# SP485.net
KiCad netlist of a schematic drawn in Altium Designer
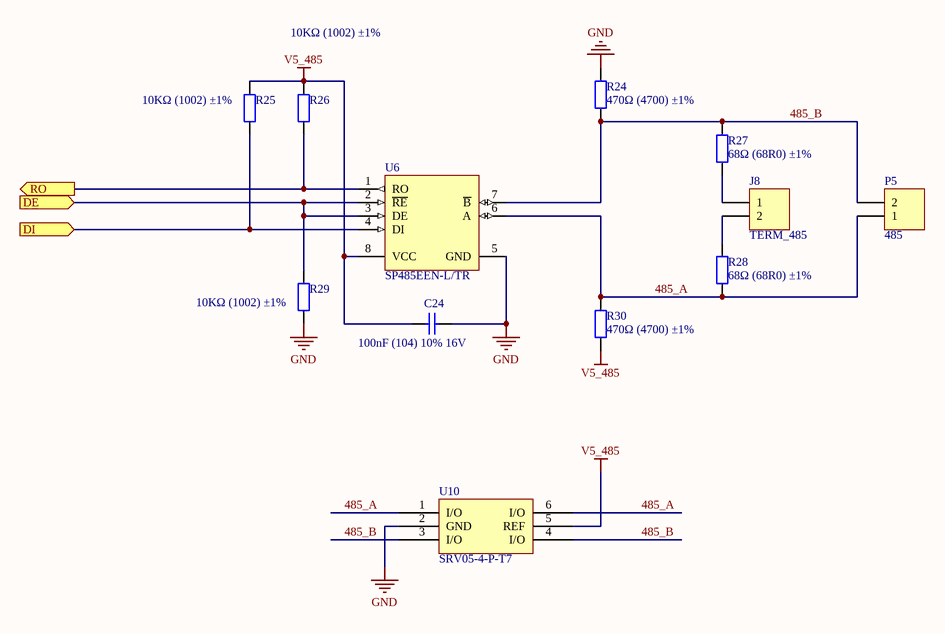
[diagram p0: SP485.SchDoc]

(export (version "E")
  (design (tool "Eeschema 10.0.6"))
  (components
    (comp (ref "C24")
      (value "100nF (104) 10% 16V")
      (footprint "0402_C")
      (description "贴片电容")
      (libsource (lib "Miscellaneous Devices LC") (part "0402 100nF (104) 10% 16V"))
    )
    (comp (ref "J8")
      (value "TERM_485")
      (footprint "HDR1X2")
      (description "Header, 2-Pin")
      (fields (field (name "PUBLISHER") "Altium Limited"))
      (libsource (lib "Miscellaneous Connectors") (part "Header 2"))
    )
    (comp (ref "P5")
      (value "485")
      (footprint "WJ2EDGRC-5.08-2PxxR")
      (description "Header, 2-Pin")
      (fields (field (name "PUBLISHER") "Altium Limited"))
      (libsource (lib "") (part "Header 2_1"))
    )
    (comp (ref "R24")
      (value "470Ω (4700) ±1%")
      (footprint "0603_R")
      (description "贴片电阻")
      (libsource (lib "Miscellaneous Devices LC") (part "0603 470Ω (4700) 1%"))
    )
    (comp (ref "R25")
      (value "10KΩ (1002) ±1%")
      (footprint "0402_R")
      (description "贴片电阻")
      (libsource (lib "Miscellaneous Devices LC") (part "0402 10KΩ (1002) 1%"))
    )
    (comp (ref "R26")
      (value "10KΩ (1002) ±1%")
      (footprint "0402_R")
      (description "贴片电阻")
      (libsource (lib "Miscellaneous Devices LC") (part "0402 10KΩ (1002) 1%"))
    )
    (comp (ref "R27")
      (value "68Ω (68R0) ±1%")
      (footprint "0603_R")
      (description "贴片电阻")
      (libsource (lib "Miscellaneous Devices LC") (part "0603 68Ω (68R0) 1%"))
    )
    (comp (ref "R28")
      (value "68Ω (68R0) ±1%")
      (footprint "0603_R")
      (description "贴片电阻")
      (libsource (lib "Miscellaneous Devices LC") (part "0603 68Ω (68R0) 1%"))
    )
    (comp (ref "R29")
      (value "10KΩ (1002) ±1%")
      (footprint "0402_R")
      (description "贴片电阻")
      (libsource (lib "Miscellaneous Devices LC") (part "0402 10KΩ (1002) 1%"))
    )
    (comp (ref "R30")
      (value "470Ω (4700) ±1%")
      (footprint "0603_R")
      (description "贴片电阻")
      (libsource (lib "Miscellaneous Devices LC") (part "0603 470Ω (4700) 1%"))
    )
    (comp (ref "U6")
      (value "SP485EEN-L/TR")
      (footprint "SOIC-8_150mil")
      (description "RS-485/RS-422")
      (libsource (lib "Miscellaneous Devices LC") (part "SP485EEN-L/TR_[C6855]"))
    )
    (comp (ref "U10")
      (value "SRV05-4-P-T7")
      (footprint "SOT-23-6")
      (description "TVS")
      (libsource (lib "Miscellaneous Devices LC") (part "SRV05-4-P-T7_[C85364]"))
    )
  )
  (nets
    (net (code "1") (name "/485_A") (class "Default")
      (node (ref "P5") (pin "1") (pinfunction "1_1") (pintype "passive"))
      (node (ref "R28") (pin "1") (pinfunction "1_1") (pintype "passive"))
      (node (ref "R30") (pin "2") (pinfunction "2_2") (pintype "passive"))
      (node (ref "U10") (pin "1") (pinfunction "I/O_1") (pintype "passive"))
      (node (ref "U10") (pin "6") (pinfunction "I/O_6") (pintype "passive"))
      (node (ref "U6") (pin "6") (pinfunction "A_6") (pintype "bidirectional"))
    )
    (net (code "2") (name "/485_B") (class "Default")
      (node (ref "P5") (pin "2") (pinfunction "2_2") (pintype "passive"))
      (node (ref "R24") (pin "1") (pinfunction "1_1") (pintype "passive"))
      (node (ref "R27") (pin "2") (pinfunction "2_2") (pintype "passive"))
      (node (ref "U10") (pin "3") (pinfunction "I/O_3") (pintype "passive"))
      (node (ref "U10") (pin "4") (pinfunction "I/O_4") (pintype "passive"))
      (node (ref "U6") (pin "7") (pinfunction "~{B}_7") (pintype "bidirectional"))
    )
    (net (code "3") (name "/DE") (class "Default")
      (node (ref "R29") (pin "1") (pinfunction "1_1") (pintype "passive"))
      (node (ref "U6") (pin "2") (pinfunction "~{RE}_2") (pintype "input"))
      (node (ref "U6") (pin "3") (pinfunction "DE_3") (pintype "input"))
    )
    (net (code "4") (name "/DI") (class "Default")
      (node (ref "R25") (pin "2") (pinfunction "2_2") (pintype "passive"))
      (node (ref "U6") (pin "4") (pinfunction "DI_4") (pintype "input"))
    )
    (net (code "5") (name "/RO") (class "Default")
      (node (ref "R26") (pin "2") (pinfunction "2_2") (pintype "passive"))
      (node (ref "U6") (pin "1") (pinfunction "RO_1") (pintype "output"))
    )
    (net (code "6") (name "GND") (class "Default")
      (node (ref "C24") (pin "1") (pinfunction "1_1") (pintype "passive"))
      (node (ref "R24") (pin "2") (pinfunction "2_2") (pintype "passive"))
      (node (ref "R29") (pin "2") (pinfunction "2_2") (pintype "passive"))
      (node (ref "U10") (pin "2") (pinfunction "GND_2") (pintype "passive"))
      (node (ref "U6") (pin "5") (pinfunction "GND_5") (pintype "power_in"))
    )
    (net (code "7") (name "Net-(J8-Pad1)") (class "Default")
      (node (ref "J8") (pin "1") (pinfunction "1_1") (pintype "passive"))
      (node (ref "R27") (pin "1") (pinfunction "1_1") (pintype "passive"))
    )
    (net (code "8") (name "Net-(J8-Pad2)") (class "Default")
      (node (ref "J8") (pin "2") (pinfunction "2_2") (pintype "passive"))
      (node (ref "R28") (pin "2") (pinfunction "2_2") (pintype "passive"))
    )
    (net (code "9") (name "V5_485") (class "Default")
      (node (ref "C24") (pin "2") (pinfunction "2_2") (pintype "passive"))
      (node (ref "R25") (pin "1") (pinfunction "1_1") (pintype "passive"))
      (node (ref "R26") (pin "1") (pinfunction "1_1") (pintype "passive"))
      (node (ref "R30") (pin "1") (pinfunction "1_1") (pintype "passive"))
      (node (ref "U10") (pin "5") (pinfunction "REF_5") (pintype "passive"))
      (node (ref "U6") (pin "8") (pinfunction "VCC_8") (pintype "power_in"))
    )
  )
)
